# MRDT0003C1.net
KiCad netlist of a schematic drawn in EAGLE
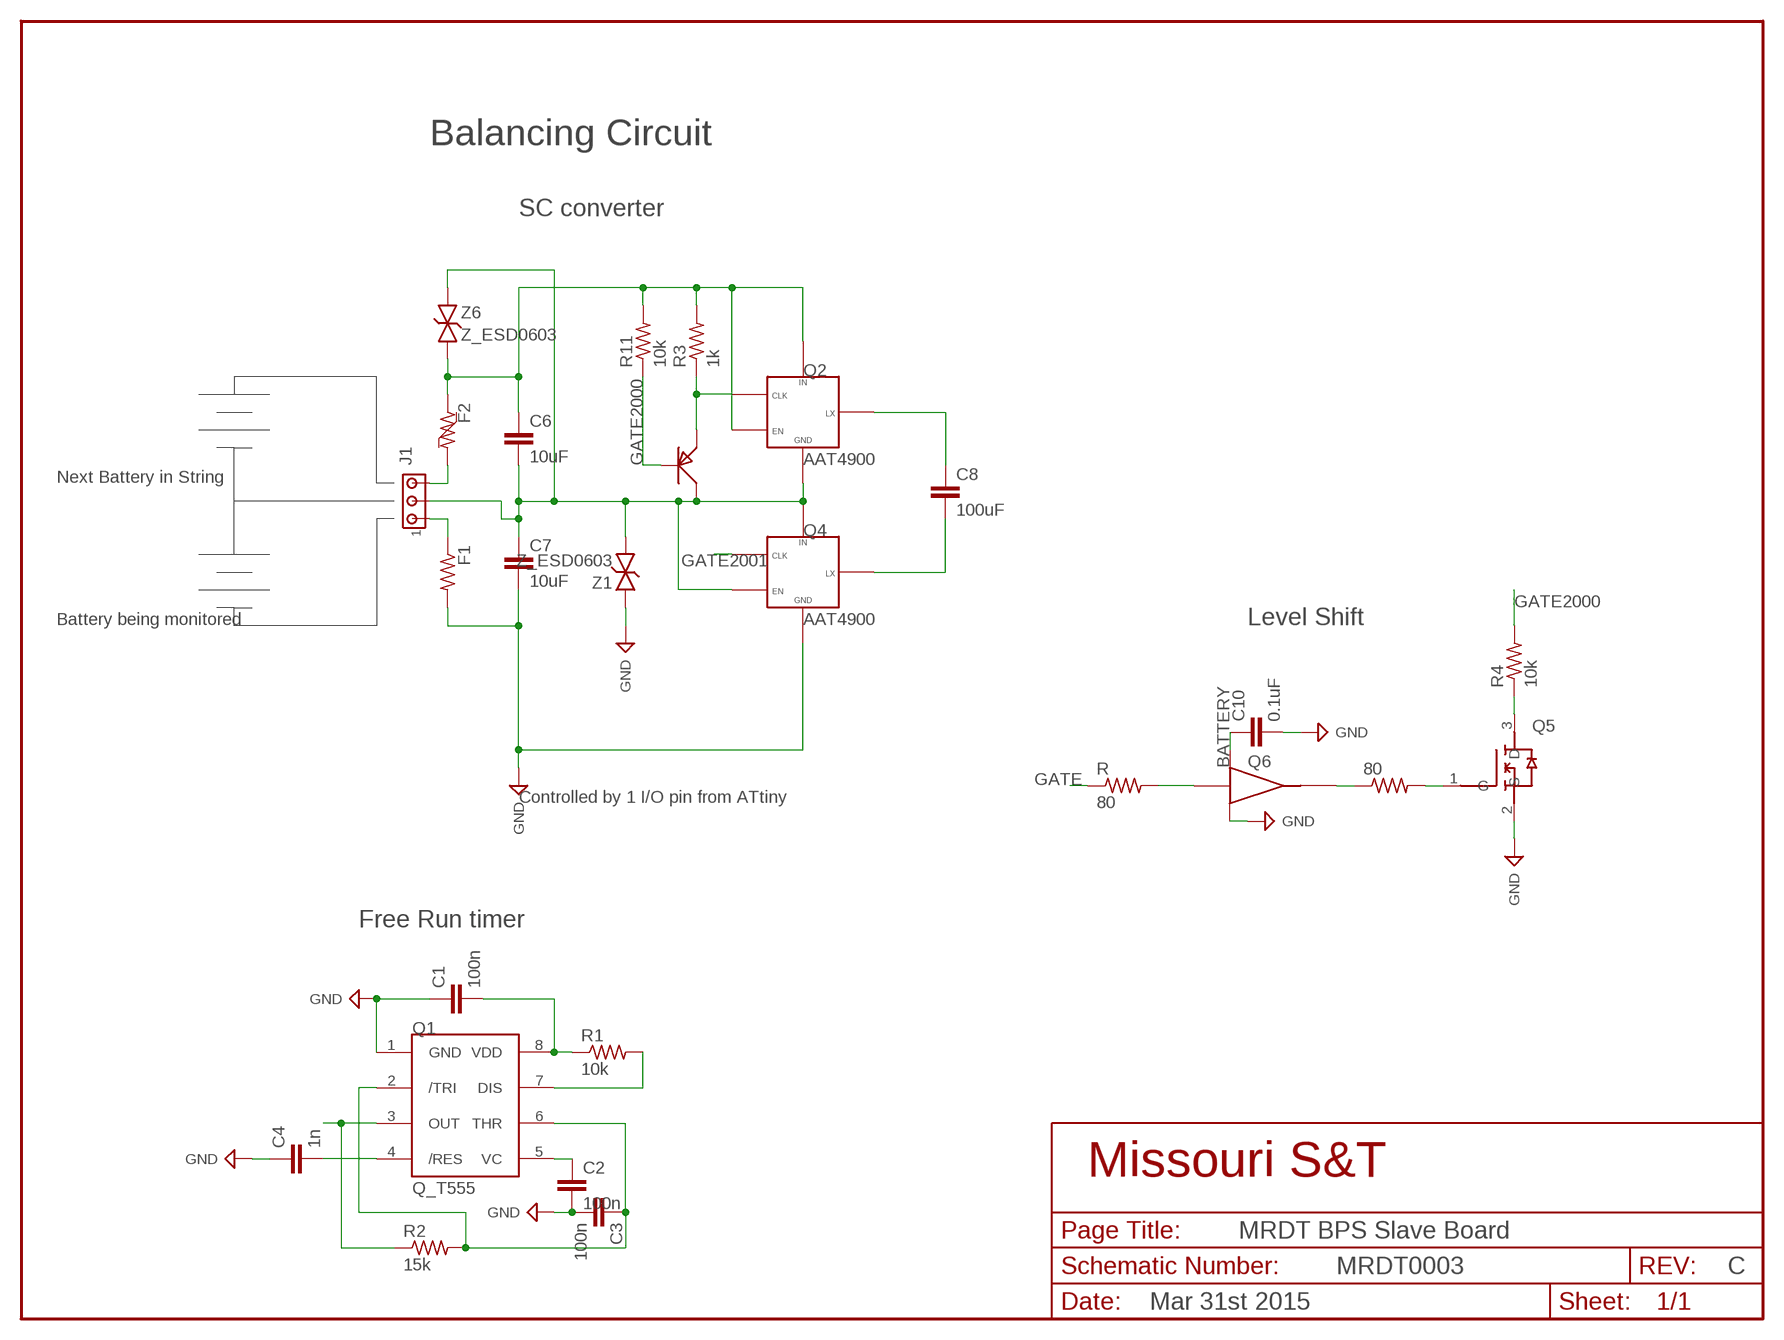
[diagram p0: schematic, sheet 1]

(export (version "E")
  (design (tool "Eeschema 10.0.6"))
  (components
    (comp (ref "80")
      (value "R_RES_1206")
      (footprint "eagle-import:R_1206")
      (libsource (lib "eagle-import") (part "R_RES_1206"))
    )
    (comp (ref "C1")
      (value "100n")
      (footprint "eagle-import:C_0603")
      (libsource (lib "eagle-import") (part "C_CAP_0603"))
    )
    (comp (ref "C2")
      (value "100n")
      (footprint "eagle-import:C_0603")
      (libsource (lib "eagle-import") (part "C_CAP_0603"))
    )
    (comp (ref "C3")
      (value "100n")
      (footprint "eagle-import:C_0603")
      (libsource (lib "eagle-import") (part "C_CAP_0603"))
    )
    (comp (ref "C4")
      (value "1n")
      (footprint "eagle-import:C_0603")
      (libsource (lib "eagle-import") (part "C_CAP_0603"))
    )
    (comp (ref "C6")
      (value "10uF")
      (footprint "eagle-import:C_1206")
      (libsource (lib "eagle-import") (part "C_CAP_1206"))
    )
    (comp (ref "C7")
      (value "10uF")
      (footprint "eagle-import:C_1206")
      (libsource (lib "eagle-import") (part "C_CAP_1206"))
    )
    (comp (ref "C8")
      (value "100uF")
      (footprint "eagle-import:C_1206")
      (libsource (lib "eagle-import") (part "Master_C_CAP_1206"))
    )
    (comp (ref "C10")
      (value "0.1uF")
      (footprint "eagle-import:C_0603")
      (libsource (lib "eagle-import") (part "C_CAP_0603"))
    )
    (comp (ref "F1")
      (value "R_RES_1210")
      (footprint "eagle-import:R_1210")
      (libsource (lib "eagle-import") (part "R_RES_1210"))
    )
    (comp (ref "F2")
      (value "R_RES_1210")
      (footprint "eagle-import:R_1210")
      (libsource (lib "eagle-import") (part "R_RES_1210"))
    )
    (comp (ref "J1")
      (value "J_HDR1X3_BRK_100MIL")
      (footprint "eagle-import:J_BRK1X3_100MIL")
      (libsource (lib "eagle-import") (part "J_HDR1X3_BRK_100MIL"))
    )
    (comp (ref "Q1")
      (value "Q_T555")
      (footprint "eagle-import:SOIC8")
      (libsource (lib "eagle-import") (part "Q_T555"))
    )
    (comp (ref "Q2")
      (value "AAT4900")
      (footprint "eagle-import:SOT-23-5")
      (libsource (lib "eagle-import") (part "Q_AAT4900"))
    )
    (comp (ref "Q4")
      (value "AAT4900")
      (footprint "eagle-import:SOT-23-5")
      (libsource (lib "eagle-import") (part "Q_AAT4900"))
    )
    (comp (ref "Q5")
      (value "N-CH-MOSFETSOT-23")
      (footprint "eagle-import:SOT-23")
      (libsource (lib "eagle-import") (part "N-CH-MOSFETSOT-23"))
    )
    (comp (ref "Q6")
      (value "Q_INVERTERSOT-23-5")
      (footprint "eagle-import:SOT-23-5")
      (libsource (lib "eagle-import") (part "Q_INVERTERSOT-23-5"))
    )
    (comp (ref "Q7")
      (value "Q_PNP")
      (footprint "eagle-import:SOT-23")
      (libsource (lib "eagle-import") (part "Q_PNP"))
    )
    (comp (ref "R")
      (value "80")
      (footprint "eagle-import:R_0603")
      (libsource (lib "eagle-import") (part "R_RES_0603"))
    )
    (comp (ref "R1")
      (value "10k")
      (footprint "eagle-import:R_0603")
      (libsource (lib "eagle-import") (part "R_RES_0603"))
    )
    (comp (ref "R2")
      (value "15k")
      (footprint "eagle-import:R_0603")
      (libsource (lib "eagle-import") (part "R_RES_0603"))
    )
    (comp (ref "R3")
      (value "1k")
      (footprint "eagle-import:R_0603")
      (libsource (lib "eagle-import") (part "R_RES_0603"))
    )
    (comp (ref "R4")
      (value "10k")
      (footprint "eagle-import:R_0603")
      (libsource (lib "eagle-import") (part "R_RES_0603"))
    )
    (comp (ref "R11")
      (value "10k")
      (footprint "eagle-import:R_0603")
      (libsource (lib "eagle-import") (part "R_RES_0603"))
    )
    (comp (ref "Z1")
      (value "Z_ESD0603")
      (footprint "eagle-import:0603")
      (libsource (lib "eagle-import") (part "Z_ESD0603"))
    )
    (comp (ref "Z6")
      (value "Z_ESD0603")
      (footprint "eagle-import:0603")
      (libsource (lib "eagle-import") (part "Z_ESD0603"))
    )
  )
  (nets
    (net (code "1") (name "/BATTERY") (class "Default")
      (node (ref "C1") (pin "2") (pinfunction "2_2") (pintype "passive"))
      (node (ref "C10") (pin "1") (pinfunction "1_1") (pintype "passive"))
      (node (ref "C4") (pin "2") (pinfunction "2_2") (pintype "passive"))
      (node (ref "C6") (pin "2") (pinfunction "2_2") (pintype "passive"))
      (node (ref "C7") (pin "1") (pinfunction "1_1") (pintype "passive"))
      (node (ref "J1") (pin "2") (pinfunction "2_2") (pintype "passive"))
      (node (ref "Q1") (pin "4") (pinfunction "/RES_4") (pintype "bidirectional"))
      (node (ref "Q1") (pin "8") (pinfunction "VDD_8") (pintype "bidirectional"))
      (node (ref "Q2") (pin "2") (pinfunction "GND_2") (pintype "bidirectional"))
      (node (ref "Q4") (pin "3") (pinfunction "EN_3") (pintype "bidirectional"))
      (node (ref "Q4") (pin "5") (pinfunction "IN_5") (pintype "bidirectional"))
      (node (ref "Q6") (pin "5") (pinfunction "VCC_5") (pintype "bidirectional"))
      (node (ref "Q7") (pin "3") (pinfunction "C_3") (pintype "bidirectional"))
      (node (ref "R1") (pin "1") (pinfunction "1_1") (pintype "passive"))
      (node (ref "Z1") (pin "1") (pinfunction "P$1_1") (pintype "bidirectional"))
      (node (ref "Z6") (pin "2") (pinfunction "P$2_2") (pintype "bidirectional"))
    )
    (net (code "2") (name "/GATE") (class "Default")
      (node (ref "Q1") (pin "3") (pinfunction "OUT_3") (pintype "bidirectional"))
      (node (ref "R") (pin "1") (pinfunction "1_1") (pintype "passive"))
      (node (ref "R2") (pin "1") (pinfunction "1_1") (pintype "passive"))
    )
    (net (code "3") (name "/GATE2000") (class "Default")
      (node (ref "Q7") (pin "1") (pinfunction "B_1") (pintype "bidirectional"))
      (node (ref "R11") (pin "1") (pinfunction "1_1") (pintype "passive"))
      (node (ref "R4") (pin "2") (pinfunction "2_2") (pintype "passive"))
    )
    (net (code "4") (name "/GATE2001") (class "Default")
      (node (ref "Q4") (pin "4") (pinfunction "CLK_4") (pintype "bidirectional"))
      (node (ref "Q6") (pin "2") (pinfunction "A_2") (pintype "bidirectional"))
      (node (ref "R") (pin "2") (pinfunction "2_2") (pintype "passive"))
    )
    (net (code "5") (name "Net-(F1-Pad1)") (class "Default")
      (node (ref "F1") (pin "1") (pinfunction "1_1") (pintype "passive"))
      (node (ref "J1") (pin "1") (pinfunction "1_1") (pintype "passive"))
    )
    (net (code "6") (name "Net-(F2-Pad2)") (class "Default")
      (node (ref "F2") (pin "2") (pinfunction "2_2") (pintype "passive"))
      (node (ref "J1") (pin "3") (pinfunction "3_3") (pintype "passive"))
    )
    (net (code "7") (name "Net-(Q1-DIS)") (class "Default")
      (node (ref "Q1") (pin "7") (pinfunction "DIS_7") (pintype "bidirectional"))
      (node (ref "R1") (pin "2") (pinfunction "2_2") (pintype "passive"))
    )
    (net (code "8") (name "Net-(Q1-THR)") (class "Default")
      (node (ref "C3") (pin "1") (pinfunction "1_1") (pintype "passive"))
      (node (ref "Q1") (pin "2") (pinfunction "/TRI_2") (pintype "bidirectional"))
      (node (ref "Q1") (pin "6") (pinfunction "THR_6") (pintype "bidirectional"))
      (node (ref "R2") (pin "2") (pinfunction "2_2") (pintype "passive"))
    )
    (net (code "9") (name "Net-(Q1-VC)") (class "Default")
      (node (ref "C2") (pin "1") (pinfunction "1_1") (pintype "passive"))
      (node (ref "Q1") (pin "5") (pinfunction "VC_5") (pintype "bidirectional"))
    )
    (net (code "10") (name "Net-(Q2-CLK)") (class "Default")
      (node (ref "Q2") (pin "4") (pinfunction "CLK_4") (pintype "bidirectional"))
      (node (ref "Q7") (pin "2") (pinfunction "E_2") (pintype "bidirectional"))
      (node (ref "R3") (pin "1") (pinfunction "1_1") (pintype "passive"))
    )
    (net (code "11") (name "Net-(Q2-EN)") (class "Default")
      (node (ref "C6") (pin "1") (pinfunction "1_1") (pintype "passive"))
      (node (ref "F2") (pin "1") (pinfunction "1_1") (pintype "passive"))
      (node (ref "Q2") (pin "3") (pinfunction "EN_3") (pintype "bidirectional"))
      (node (ref "Q2") (pin "5") (pinfunction "IN_5") (pintype "bidirectional"))
      (node (ref "R11") (pin "2") (pinfunction "2_2") (pintype "passive"))
      (node (ref "R3") (pin "2") (pinfunction "2_2") (pintype "passive"))
      (node (ref "Z6") (pin "1") (pinfunction "P$1_1") (pintype "bidirectional"))
    )
    (net (code "12") (name "Net-(Q2-LX)") (class "Default")
      (node (ref "C8") (pin "1") (pinfunction "1_1") (pintype "passive"))
      (node (ref "Q2") (pin "1") (pinfunction "LX_1") (pintype "bidirectional"))
    )
    (net (code "13") (name "Net-(Q4-LX)") (class "Default")
      (node (ref "C8") (pin "2") (pinfunction "2_2") (pintype "passive"))
      (node (ref "Q4") (pin "1") (pinfunction "LX_1") (pintype "bidirectional"))
    )
    (net (code "14") (name "Net-(Q5-D)") (class "Default")
      (node (ref "Q5") (pin "3") (pinfunction "D_3") (pintype "bidirectional"))
      (node (ref "R4") (pin "1") (pinfunction "1_1") (pintype "passive"))
    )
    (net (code "15") (name "Net-(Q5-G)") (class "Default")
      (node (ref "80") (pin "2") (pinfunction "2_2") (pintype "passive"))
      (node (ref "Q5") (pin "1") (pinfunction "G_1") (pintype "bidirectional"))
    )
    (net (code "16") (name "Net-(Q6-Y)") (class "Default")
      (node (ref "80") (pin "1") (pinfunction "1_1") (pintype "passive"))
      (node (ref "Q6") (pin "4") (pinfunction "Y_4") (pintype "bidirectional"))
    )
    (net (code "17") (name "SUP_GND") (class "Default")
      (node (ref "C1") (pin "1") (pinfunction "1_1") (pintype "passive"))
      (node (ref "C10") (pin "2") (pinfunction "2_2") (pintype "passive"))
      (node (ref "C2") (pin "2") (pinfunction "2_2") (pintype "passive"))
      (node (ref "C3") (pin "2") (pinfunction "2_2") (pintype "passive"))
      (node (ref "C4") (pin "1") (pinfunction "1_1") (pintype "passive"))
      (node (ref "C7") (pin "2") (pinfunction "2_2") (pintype "passive"))
      (node (ref "F1") (pin "2") (pinfunction "2_2") (pintype "passive"))
      (node (ref "Q1") (pin "1") (pinfunction "GND_1") (pintype "bidirectional"))
      (node (ref "Q4") (pin "2") (pinfunction "GND_2") (pintype "bidirectional"))
      (node (ref "Q5") (pin "2") (pinfunction "S_2") (pintype "bidirectional"))
      (node (ref "Q6") (pin "3") (pinfunction "GND_3") (pintype "bidirectional"))
      (node (ref "Z1") (pin "2") (pinfunction "P$2_2") (pintype "bidirectional"))
    )
  )
)
